# 5_Fans_Control.net
KiCad netlist of a schematic drawn in Altium Designer
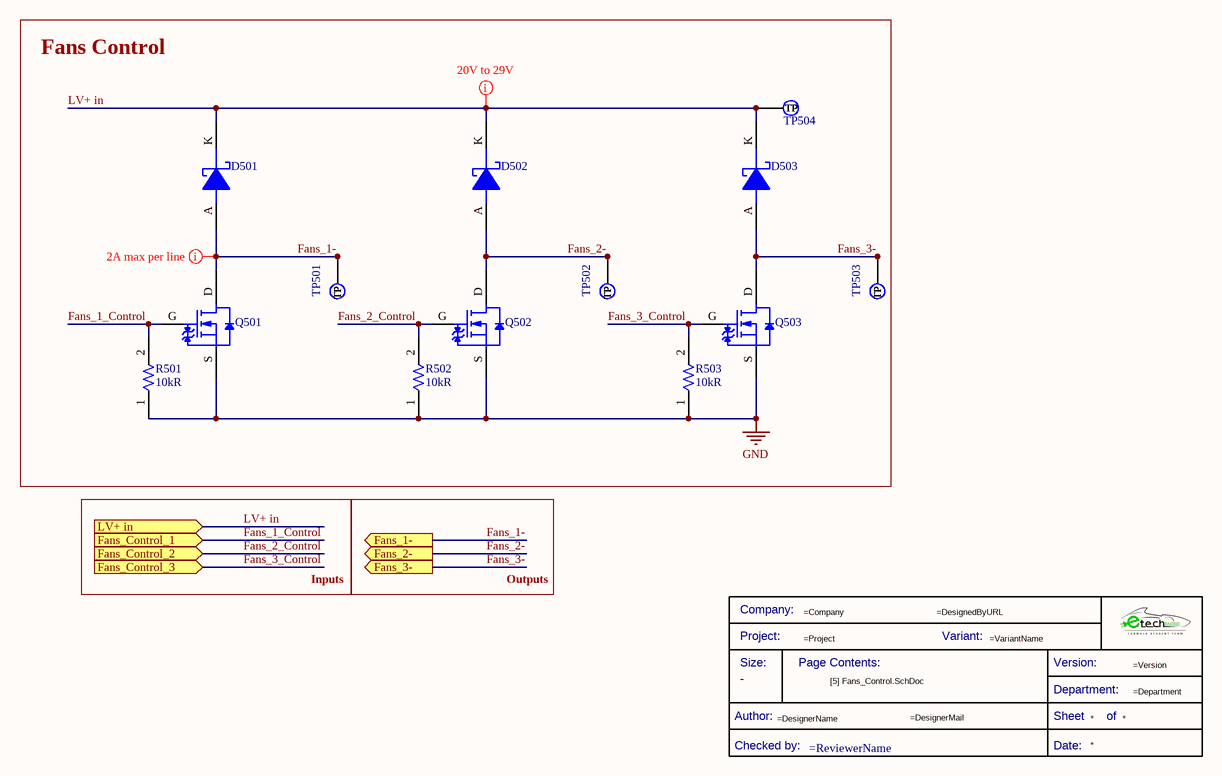
[diagram p0: [5] Fans_Control.SchDoc]

(export (version "E")
  (design (tool "Eeschema 10.0.6"))
  (components
    (comp (ref "*")
      (value "Title Block_template")
      (description "Standard Title Block")
      (fields (field (name "SIZE") "-"))
      (libsource (lib "e-Tech_Racing") (part "Title Block_template"))
    )
    (comp (ref "D501")
      (value "MBR0530")
      (footprint "DSC-SOD123")
      (description "VR=30V IF=500mA 30pF P=410mW")
      (fields (field (name ".CREATOR") "GP"))
      (libsource (lib "Filter components") (part "DSC-0.5/30-SOD123"))
    )
    (comp (ref "D502")
      (value "MBR0530")
      (footprint "DSC-SOD123")
      (description "VR=30V IF=500mA 30pF P=410mW")
      (fields (field (name ".CREATOR") "GP"))
      (libsource (lib "Filter components") (part "DSC-0.5/30-SOD123"))
    )
    (comp (ref "D503")
      (value "MBR0530")
      (footprint "DSC-SOD123")
      (description "VR=30V IF=500mA 30pF P=410mW")
      (fields (field (name ".CREATOR") "GP"))
      (libsource (lib "Filter components") (part "DSC-0.5/30-SOD123"))
    )
    (comp (ref "Q501")
      (value "CPH3455-TL-H")
      (footprint "TRT-NCH-3/35-CPH")
      (description "CPH3455-TL-H N-channel MOSFET Transistor; 3 A; 35 V; 3-Pin CPH")
      (fields (field (name "MANUFACTURER") "ON Semiconductor") (field (name ".CREATOR") "GP"))
      (libsource (lib "Semiconductor") (part "TRT-NCH-3/35-CPH"))
    )
    (comp (ref "Q502")
      (value "CPH3455-TL-H")
      (footprint "TRT-NCH-3/35-CPH")
      (description "CPH3455-TL-H N-channel MOSFET Transistor; 3 A; 35 V; 3-Pin CPH")
      (fields (field (name "MANUFACTURER") "ON Semiconductor") (field (name ".CREATOR") "GP"))
      (libsource (lib "Semiconductor") (part "TRT-NCH-3/35-CPH"))
    )
    (comp (ref "Q503")
      (value "CPH3455-TL-H")
      (footprint "TRT-NCH-3/35-CPH")
      (description "CPH3455-TL-H N-channel MOSFET Transistor; 3 A; 35 V; 3-Pin CPH")
      (fields (field (name "MANUFACTURER") "ON Semiconductor") (field (name ".CREATOR") "GP"))
      (libsource (lib "Semiconductor") (part "TRT-NCH-3/35-CPH"))
    )
    (comp (ref "R501")
      (value "CR0805-JW-103ELF")
      (footprint "R0805FTK")
      (fields
        (field (name "TOLERANCE") "5%")
        (field (name "RESISTANCE") "10kR")
        (field (name ".CREATOR") "DR")
      )
      (libsource (lib "Passives") (part "R10k-0805FTK"))
    )
    (comp (ref "R502")
      (value "CR0805-JW-103ELF")
      (footprint "R0805FTK")
      (fields
        (field (name "TOLERANCE") "5%")
        (field (name "RESISTANCE") "10kR")
        (field (name ".CREATOR") "DR")
      )
      (libsource (lib "Passives") (part "R10k-0805FTK"))
    )
    (comp (ref "R503")
      (value "CR0805-JW-103ELF")
      (footprint "R0805FTK")
      (fields
        (field (name "TOLERANCE") "5%")
        (field (name "RESISTANCE") "10kR")
        (field (name ".CREATOR") "DR")
      )
      (libsource (lib "Passives") (part "R10k-0805FTK"))
    )
    (comp (ref "TP501")
      (value "TestPoint")
      (footprint "TestPoint")
      (description "Test Point 1x1 mm")
      (fields (field (name ".CREATOR") "GP") (field (name ".PCBCHECK") "GP") (field (name ".SCHCHECK") "GP"))
      (libsource (lib "e-Tech_Racing") (part "TestPoint"))
    )
    (comp (ref "TP502")
      (value "TestPoint")
      (footprint "TestPoint")
      (description "Test Point 1x1 mm")
      (fields (field (name ".CREATOR") "GP") (field (name ".PCBCHECK") "GP") (field (name ".SCHCHECK") "GP"))
      (libsource (lib "e-Tech_Racing") (part "TestPoint"))
    )
    (comp (ref "TP503")
      (value "TestPoint")
      (footprint "TestPoint")
      (description "Test Point 1x1 mm")
      (fields (field (name ".CREATOR") "GP") (field (name ".PCBCHECK") "GP") (field (name ".SCHCHECK") "GP"))
      (libsource (lib "e-Tech_Racing") (part "TestPoint"))
    )
    (comp (ref "TP504")
      (value "TestPoint")
      (footprint "TestPoint")
      (description "Test Point 1x1 mm")
      (fields (field (name ".CREATOR") "GP") (field (name ".PCBCHECK") "GP") (field (name ".SCHCHECK") "GP"))
      (libsource (lib "e-Tech_Racing") (part "TestPoint"))
    )
  )
  (nets
    (net (code "1") (name "/Fans_1-") (class "Default")
      (node (ref "D501") (pin "A") (pinfunction "A_A") (pintype "passive"))
      (node (ref "Q501") (pin "D") (pinfunction "D_D") (pintype "passive"))
      (node (ref "TP501") (pin "1") (pinfunction "TP_1") (pintype "passive"))
    )
    (net (code "2") (name "/Fans_1_Control") (class "Default")
      (node (ref "Q501") (pin "G") (pinfunction "G_G") (pintype "passive"))
      (node (ref "R501") (pin "2") (pinfunction "2_2") (pintype "passive"))
    )
    (net (code "3") (name "/Fans_2-") (class "Default")
      (node (ref "D502") (pin "A") (pinfunction "A_A") (pintype "passive"))
      (node (ref "Q502") (pin "D") (pinfunction "D_D") (pintype "passive"))
      (node (ref "TP502") (pin "1") (pinfunction "TP_1") (pintype "passive"))
    )
    (net (code "4") (name "/Fans_2_Control") (class "Default")
      (node (ref "Q502") (pin "G") (pinfunction "G_G") (pintype "passive"))
      (node (ref "R502") (pin "2") (pinfunction "2_2") (pintype "passive"))
    )
    (net (code "5") (name "/Fans_3-") (class "Default")
      (node (ref "D503") (pin "A") (pinfunction "A_A") (pintype "passive"))
      (node (ref "Q503") (pin "D") (pinfunction "D_D") (pintype "passive"))
      (node (ref "TP503") (pin "1") (pinfunction "TP_1") (pintype "passive"))
    )
    (net (code "6") (name "/Fans_3_Control") (class "Default")
      (node (ref "Q503") (pin "G") (pinfunction "G_G") (pintype "passive"))
      (node (ref "R503") (pin "2") (pinfunction "2_2") (pintype "passive"))
    )
    (net (code "7") (name "/LV+ in") (class "Default")
      (node (ref "D501") (pin "K") (pinfunction "K_K") (pintype "passive"))
      (node (ref "D502") (pin "K") (pinfunction "K_K") (pintype "passive"))
      (node (ref "D503") (pin "K") (pinfunction "K_K") (pintype "passive"))
      (node (ref "TP504") (pin "1") (pinfunction "TP_1") (pintype "passive"))
    )
    (net (code "8") (name "GND") (class "Default")
      (node (ref "Q501") (pin "S") (pinfunction "S_S") (pintype "passive"))
      (node (ref "Q502") (pin "S") (pinfunction "S_S") (pintype "passive"))
      (node (ref "Q503") (pin "S") (pinfunction "S_S") (pintype "passive"))
      (node (ref "R501") (pin "1") (pinfunction "1_1") (pintype "passive"))
      (node (ref "R502") (pin "1") (pinfunction "1_1") (pintype "passive"))
      (node (ref "R503") (pin "1") (pinfunction "1_1") (pintype "passive"))
    )
  )
)
